# Memory_Connector.net
KiCad netlist of a schematic drawn in Altium Designer
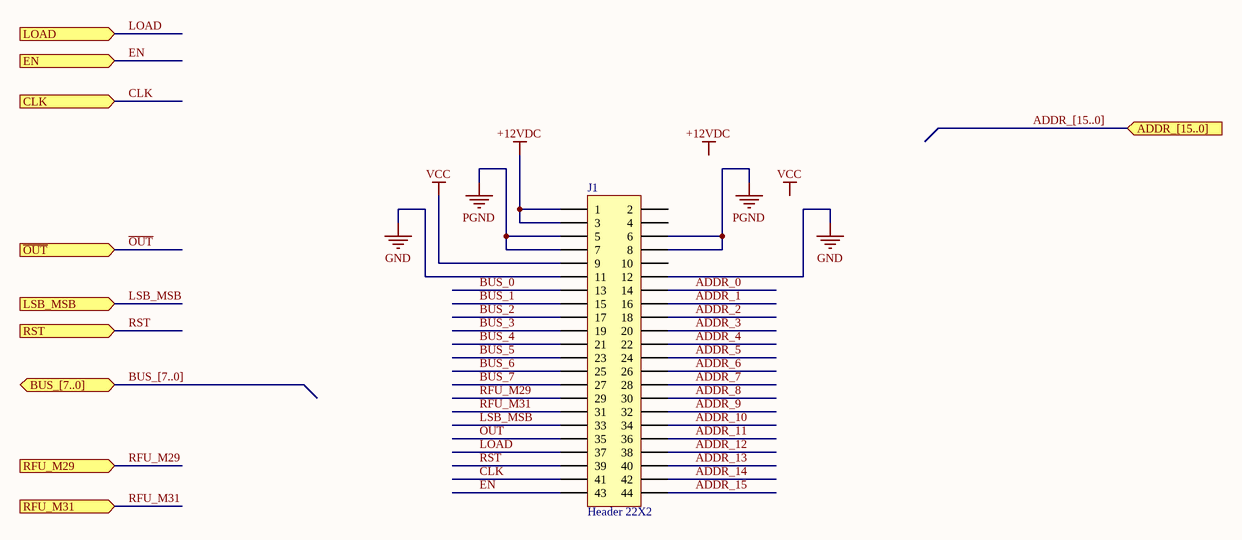
[diagram p0: Memory Connector.SchDoc]

(export (version "E")
  (design (tool "Eeschema 10.0.6"))
  (components
    (comp (ref "J1")
      (value "Header 22X2")
      (footprint "HDR2X22")
      (description "Header, 22-Pin, Dual row")
      (fields (field (name "PUBLISHER") "Altium Limited"))
      (libsource (lib "Miscellaneous Connectors") (part "Header 22X2"))
    )
  )
  (nets
    (net (code "1") (name "+12VDC") (class "Default")
      (node (ref "J1") (pin "1") (pinfunction "1_1") (pintype "passive"))
      (node (ref "J1") (pin "3") (pinfunction "3_3") (pintype "passive"))
    )
    (net (code "2") (name "/ADDR_0") (class "Default")
      (node (ref "J1") (pin "14") (pinfunction "14_14") (pintype "passive"))
    )
    (net (code "3") (name "/ADDR_1") (class "Default")
      (node (ref "J1") (pin "16") (pinfunction "16_16") (pintype "passive"))
    )
    (net (code "4") (name "/ADDR_2") (class "Default")
      (node (ref "J1") (pin "18") (pinfunction "18_18") (pintype "passive"))
    )
    (net (code "5") (name "/ADDR_3") (class "Default")
      (node (ref "J1") (pin "20") (pinfunction "20_20") (pintype "passive"))
    )
    (net (code "6") (name "/ADDR_4") (class "Default")
      (node (ref "J1") (pin "22") (pinfunction "22_22") (pintype "passive"))
    )
    (net (code "7") (name "/ADDR_5") (class "Default")
      (node (ref "J1") (pin "24") (pinfunction "24_24") (pintype "passive"))
    )
    (net (code "8") (name "/ADDR_6") (class "Default")
      (node (ref "J1") (pin "26") (pinfunction "26_26") (pintype "passive"))
    )
    (net (code "9") (name "/ADDR_7") (class "Default")
      (node (ref "J1") (pin "28") (pinfunction "28_28") (pintype "passive"))
    )
    (net (code "10") (name "/ADDR_8") (class "Default")
      (node (ref "J1") (pin "30") (pinfunction "30_30") (pintype "passive"))
    )
    (net (code "11") (name "/ADDR_9") (class "Default")
      (node (ref "J1") (pin "32") (pinfunction "32_32") (pintype "passive"))
    )
    (net (code "12") (name "/ADDR_10") (class "Default")
      (node (ref "J1") (pin "34") (pinfunction "34_34") (pintype "passive"))
    )
    (net (code "13") (name "/ADDR_11") (class "Default")
      (node (ref "J1") (pin "36") (pinfunction "36_36") (pintype "passive"))
    )
    (net (code "14") (name "/ADDR_12") (class "Default")
      (node (ref "J1") (pin "38") (pinfunction "38_38") (pintype "passive"))
    )
    (net (code "15") (name "/ADDR_13") (class "Default")
      (node (ref "J1") (pin "40") (pinfunction "40_40") (pintype "passive"))
    )
    (net (code "16") (name "/ADDR_14") (class "Default")
      (node (ref "J1") (pin "42") (pinfunction "42_42") (pintype "passive"))
    )
    (net (code "17") (name "/ADDR_15") (class "Default")
      (node (ref "J1") (pin "44") (pinfunction "44_44") (pintype "passive"))
    )
    (net (code "19") (name "/BUS_0") (class "Default")
      (node (ref "J1") (pin "13") (pinfunction "13_13") (pintype "passive"))
    )
    (net (code "20") (name "/BUS_1") (class "Default")
      (node (ref "J1") (pin "15") (pinfunction "15_15") (pintype "passive"))
    )
    (net (code "21") (name "/BUS_2") (class "Default")
      (node (ref "J1") (pin "17") (pinfunction "17_17") (pintype "passive"))
    )
    (net (code "22") (name "/BUS_3") (class "Default")
      (node (ref "J1") (pin "19") (pinfunction "19_19") (pintype "passive"))
    )
    (net (code "23") (name "/BUS_4") (class "Default")
      (node (ref "J1") (pin "21") (pinfunction "21_21") (pintype "passive"))
    )
    (net (code "24") (name "/BUS_5") (class "Default")
      (node (ref "J1") (pin "23") (pinfunction "23_23") (pintype "passive"))
    )
    (net (code "25") (name "/BUS_6") (class "Default")
      (node (ref "J1") (pin "25") (pinfunction "25_25") (pintype "passive"))
    )
    (net (code "26") (name "/BUS_7") (class "Default")
      (node (ref "J1") (pin "27") (pinfunction "27_27") (pintype "passive"))
    )
    (net (code "28") (name "/CLK") (class "Default")
      (node (ref "J1") (pin "41") (pinfunction "41_41") (pintype "passive"))
    )
    (net (code "29") (name "/EN") (class "Default")
      (node (ref "J1") (pin "43") (pinfunction "43_43") (pintype "passive"))
    )
    (net (code "30") (name "/LOAD") (class "Default")
      (node (ref "J1") (pin "37") (pinfunction "37_37") (pintype "passive"))
    )
    (net (code "31") (name "/LSB_MSB") (class "Default")
      (node (ref "J1") (pin "33") (pinfunction "33_33") (pintype "passive"))
    )
    (net (code "32") (name "/RFU_M29") (class "Default")
      (node (ref "J1") (pin "29") (pinfunction "29_29") (pintype "passive"))
    )
    (net (code "33") (name "/RFU_M31") (class "Default")
      (node (ref "J1") (pin "31") (pinfunction "31_31") (pintype "passive"))
    )
    (net (code "34") (name "/RST") (class "Default")
      (node (ref "J1") (pin "39") (pinfunction "39_39") (pintype "passive"))
    )
    (net (code "35") (name "/~{OUT}") (class "Default")
      (node (ref "J1") (pin "35") (pinfunction "35_35") (pintype "passive"))
    )
    (net (code "36") (name "GND") (class "Default")
      (node (ref "J1") (pin "11") (pinfunction "11_11") (pintype "passive"))
      (node (ref "J1") (pin "12") (pinfunction "12_12") (pintype "passive"))
    )
    (net (code "37") (name "PGND") (class "Default")
      (node (ref "J1") (pin "5") (pinfunction "5_5") (pintype "passive"))
      (node (ref "J1") (pin "6") (pinfunction "6_6") (pintype "passive"))
      (node (ref "J1") (pin "7") (pinfunction "7_7") (pintype "passive"))
      (node (ref "J1") (pin "8") (pinfunction "8_8") (pintype "passive"))
    )
    (net (code "38") (name "VCC") (class "Default")
      (node (ref "J1") (pin "9") (pinfunction "9_9") (pintype "passive"))
    )
    (net (code "39") (name "unconnected-(J1-Pad2)") (class "Default")
      (node (ref "J1") (pin "2") (pinfunction "2_2") (pintype "passive"))
    )
    (net (code "40") (name "unconnected-(J1-Pad4)") (class "Default")
      (node (ref "J1") (pin "4") (pinfunction "4_4") (pintype "passive"))
    )
    (net (code "41") (name "unconnected-(J1-Pad10)") (class "Default")
      (node (ref "J1") (pin "10") (pinfunction "10_10") (pintype "passive"))
    )
  )
)
